# 1-Schematic_business_card_v1.net
KiCad netlist of a schematic drawn in EasyEDA
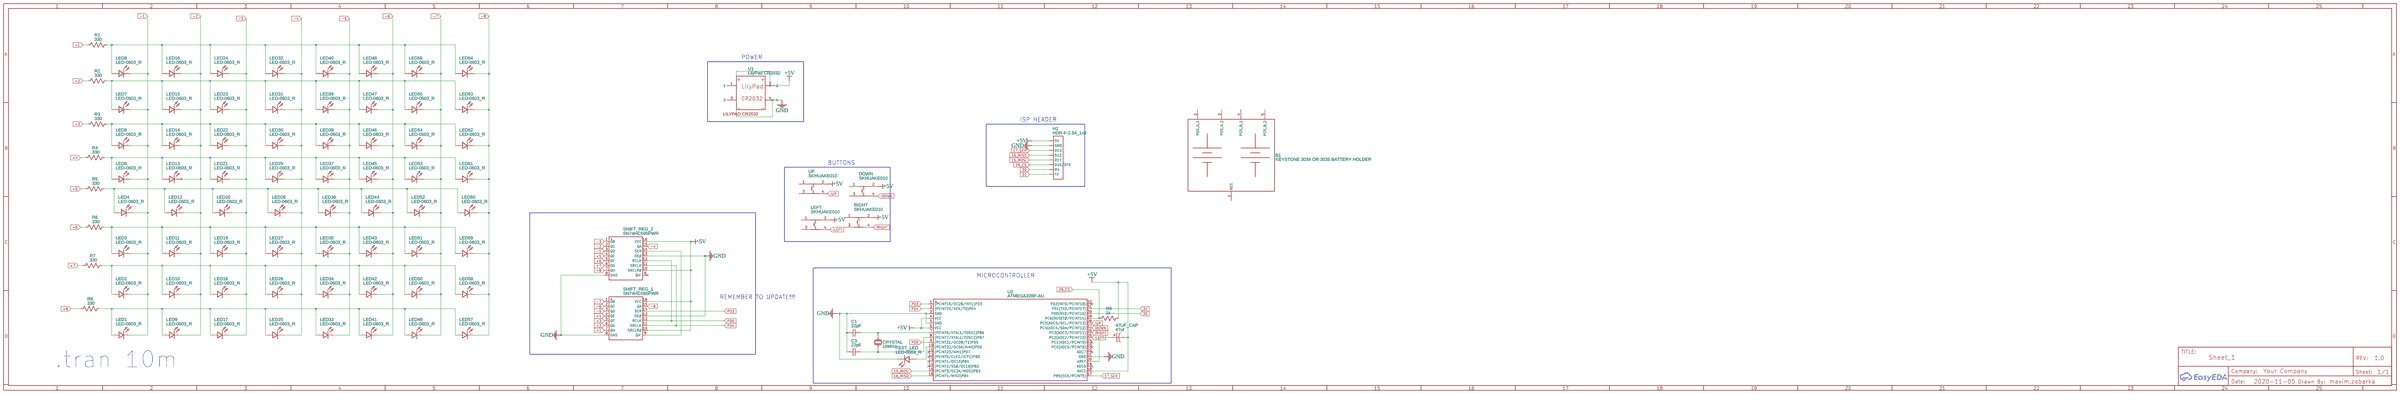
[diagram p0: schematic sheet]

(export (version "E")
  (design (tool "Eeschema 10.0.6"))
  (components
    (comp (ref "47UF_CAP") (value "47uf") (libsource (lib "") (part "C_Tan_SMD_A_US")))
    (comp (ref "B1")
      (value "KEYSTONE 3034 OR 3035 BATTERY HOLDER")
      (libsource (lib "") (part "KEYSTONE 3034 OR 3035 BATTERY HOLDER"))
    )
    (comp (ref "C1")
      (value "22pF")
      (fields
        (field (name "BOM_Manufacturer Part") "CC1206JKNPOCBN220")
        (field (name "BOM_Supplier Part") "C107174")
      )
      (libsource (lib "") (part "CC1206JKNPOCBN220"))
    )
    (comp (ref "C3")
      (value "22pF")
      (fields
        (field (name "BOM_Manufacturer Part") "CC1206JKNPOCBN220")
        (field (name "BOM_Supplier Part") "C107174")
      )
      (libsource (lib "") (part "CC1206JKNPOCBN220"))
    )
    (comp (ref "CRYSTAL")
      (value "16MHz")
      (fields
        (field (name "BOM_Manufacturer Part") "C16000J119")
        (field (name "BOM_Supplier Part") "C259047")
      )
      (libsource (lib "") (part "C16000J119"))
    )
    (comp (ref "DOWN")
      (value "SKHUAKE010")
      (fields (field (name "BOM_Supplier Part") "C262397"))
      (libsource (lib "") (part "SKHUAKE010"))
    )
    (comp (ref "H2")
      (value "HDR-F-2.54_1x8")
      (fields (field (name "BOM_Supplier Part") "C225505"))
      (libsource (lib "") (part "HDR-F-2.54_1x8"))
    )
    (comp (ref "LED1")
      (value "LED-0603_R")
      (fields
        (field (name "BOM_Manufacturer Part") "19-217/R6C-AL1M2VY/3T")
        (field (name "BOM_Supplier Part") "C72044")
      )
      (libsource (lib "") (part "LED-0603_R"))
    )
    (comp (ref "LED2")
      (value "LED-0603_R")
      (fields
        (field (name "BOM_Manufacturer Part") "19-217/R6C-AL1M2VY/3T")
        (field (name "BOM_Supplier Part") "C72044")
      )
      (libsource (lib "") (part "LED-0603_R"))
    )
    (comp (ref "LED3")
      (value "LED-0603_R")
      (fields
        (field (name "BOM_Manufacturer Part") "19-217/R6C-AL1M2VY/3T")
        (field (name "BOM_Supplier Part") "C72044")
      )
      (libsource (lib "") (part "LED-0603_R"))
    )
    (comp (ref "LED4")
      (value "LED-0603_R")
      (fields
        (field (name "BOM_Manufacturer Part") "19-217/R6C-AL1M2VY/3T")
        (field (name "BOM_Supplier Part") "C72044")
      )
      (libsource (lib "") (part "LED-0603_R"))
    )
    (comp (ref "LED5")
      (value "LED-0603_R")
      (fields
        (field (name "BOM_Manufacturer Part") "19-217/R6C-AL1M2VY/3T")
        (field (name "BOM_Supplier Part") "C72044")
      )
      (libsource (lib "") (part "LED-0603_R"))
    )
    (comp (ref "LED6")
      (value "LED-0603_R")
      (fields
        (field (name "BOM_Manufacturer Part") "19-217/R6C-AL1M2VY/3T")
        (field (name "BOM_Supplier Part") "C72044")
      )
      (libsource (lib "") (part "LED-0603_R"))
    )
    (comp (ref "LED7")
      (value "LED-0603_R")
      (fields
        (field (name "BOM_Manufacturer Part") "19-217/R6C-AL1M2VY/3T")
        (field (name "BOM_Supplier Part") "C72044")
      )
      (libsource (lib "") (part "LED-0603_R"))
    )
    (comp (ref "LED8")
      (value "LED-0603_R")
      (fields
        (field (name "BOM_Manufacturer Part") "19-217/R6C-AL1M2VY/3T")
        (field (name "BOM_Supplier Part") "C72044")
      )
      (libsource (lib "") (part "LED-0603_R"))
    )
    (comp (ref "LED9")
      (value "LED-0603_R")
      (fields
        (field (name "BOM_Manufacturer Part") "19-217/R6C-AL1M2VY/3T")
        (field (name "BOM_Supplier Part") "C72044")
      )
      (libsource (lib "") (part "LED-0603_R"))
    )
    (comp (ref "LED10")
      (value "LED-0603_R")
      (fields
        (field (name "BOM_Manufacturer Part") "19-217/R6C-AL1M2VY/3T")
        (field (name "BOM_Supplier Part") "C72044")
      )
      (libsource (lib "") (part "LED-0603_R"))
    )
    (comp (ref "LED11")
      (value "LED-0603_R")
      (fields
        (field (name "BOM_Manufacturer Part") "19-217/R6C-AL1M2VY/3T")
        (field (name "BOM_Supplier Part") "C72044")
      )
      (libsource (lib "") (part "LED-0603_R"))
    )
    (comp (ref "LED12")
      (value "LED-0603_R")
      (fields
        (field (name "BOM_Manufacturer Part") "19-217/R6C-AL1M2VY/3T")
        (field (name "BOM_Supplier Part") "C72044")
      )
      (libsource (lib "") (part "LED-0603_R"))
    )
    (comp (ref "LED13")
      (value "LED-0603_R")
      (fields
        (field (name "BOM_Manufacturer Part") "19-217/R6C-AL1M2VY/3T")
        (field (name "BOM_Supplier Part") "C72044")
      )
      (libsource (lib "") (part "LED-0603_R"))
    )
    (comp (ref "LED14")
      (value "LED-0603_R")
      (fields
        (field (name "BOM_Manufacturer Part") "19-217/R6C-AL1M2VY/3T")
        (field (name "BOM_Supplier Part") "C72044")
      )
      (libsource (lib "") (part "LED-0603_R"))
    )
    (comp (ref "LED15")
      (value "LED-0603_R")
      (fields
        (field (name "BOM_Manufacturer Part") "19-217/R6C-AL1M2VY/3T")
        (field (name "BOM_Supplier Part") "C72044")
      )
      (libsource (lib "") (part "LED-0603_R"))
    )
    (comp (ref "LED16")
      (value "LED-0603_R")
      (fields
        (field (name "BOM_Manufacturer Part") "19-217/R6C-AL1M2VY/3T")
        (field (name "BOM_Supplier Part") "C72044")
      )
      (libsource (lib "") (part "LED-0603_R"))
    )
    (comp (ref "LED17")
      (value "LED-0603_R")
      (fields
        (field (name "BOM_Manufacturer Part") "19-217/R6C-AL1M2VY/3T")
        (field (name "BOM_Supplier Part") "C72044")
      )
      (libsource (lib "") (part "LED-0603_R"))
    )
    (comp (ref "LED18")
      (value "LED-0603_R")
      (fields
        (field (name "BOM_Manufacturer Part") "19-217/R6C-AL1M2VY/3T")
        (field (name "BOM_Supplier Part") "C72044")
      )
      (libsource (lib "") (part "LED-0603_R"))
    )
    (comp (ref "LED19")
      (value "LED-0603_R")
      (fields
        (field (name "BOM_Manufacturer Part") "19-217/R6C-AL1M2VY/3T")
        (field (name "BOM_Supplier Part") "C72044")
      )
      (libsource (lib "") (part "LED-0603_R"))
    )
    (comp (ref "LED20")
      (value "LED-0603_R")
      (fields
        (field (name "BOM_Manufacturer Part") "19-217/R6C-AL1M2VY/3T")
        (field (name "BOM_Supplier Part") "C72044")
      )
      (libsource (lib "") (part "LED-0603_R"))
    )
    (comp (ref "LED21")
      (value "LED-0603_R")
      (fields
        (field (name "BOM_Manufacturer Part") "19-217/R6C-AL1M2VY/3T")
        (field (name "BOM_Supplier Part") "C72044")
      )
      (libsource (lib "") (part "LED-0603_R"))
    )
    (comp (ref "LED22")
      (value "LED-0603_R")
      (fields
        (field (name "BOM_Manufacturer Part") "19-217/R6C-AL1M2VY/3T")
        (field (name "BOM_Supplier Part") "C72044")
      )
      (libsource (lib "") (part "LED-0603_R"))
    )
    (comp (ref "LED23")
      (value "LED-0603_R")
      (fields
        (field (name "BOM_Manufacturer Part") "19-217/R6C-AL1M2VY/3T")
        (field (name "BOM_Supplier Part") "C72044")
      )
      (libsource (lib "") (part "LED-0603_R"))
    )
    (comp (ref "LED24")
      (value "LED-0603_R")
      (fields
        (field (name "BOM_Manufacturer Part") "19-217/R6C-AL1M2VY/3T")
        (field (name "BOM_Supplier Part") "C72044")
      )
      (libsource (lib "") (part "LED-0603_R"))
    )
    (comp (ref "LED25")
      (value "LED-0603_R")
      (fields
        (field (name "BOM_Manufacturer Part") "19-217/R6C-AL1M2VY/3T")
        (field (name "BOM_Supplier Part") "C72044")
      )
      (libsource (lib "") (part "LED-0603_R"))
    )
    (comp (ref "LED26")
      (value "LED-0603_R")
      (fields
        (field (name "BOM_Manufacturer Part") "19-217/R6C-AL1M2VY/3T")
        (field (name "BOM_Supplier Part") "C72044")
      )
      (libsource (lib "") (part "LED-0603_R"))
    )
    (comp (ref "LED27")
      (value "LED-0603_R")
      (fields
        (field (name "BOM_Manufacturer Part") "19-217/R6C-AL1M2VY/3T")
        (field (name "BOM_Supplier Part") "C72044")
      )
      (libsource (lib "") (part "LED-0603_R"))
    )
    (comp (ref "LED28")
      (value "LED-0603_R")
      (fields
        (field (name "BOM_Manufacturer Part") "19-217/R6C-AL1M2VY/3T")
        (field (name "BOM_Supplier Part") "C72044")
      )
      (libsource (lib "") (part "LED-0603_R"))
    )
    (comp (ref "LED29")
      (value "LED-0603_R")
      (fields
        (field (name "BOM_Manufacturer Part") "19-217/R6C-AL1M2VY/3T")
        (field (name "BOM_Supplier Part") "C72044")
      )
      (libsource (lib "") (part "LED-0603_R"))
    )
    (comp (ref "LED30")
      (value "LED-0603_R")
      (fields
        (field (name "BOM_Manufacturer Part") "19-217/R6C-AL1M2VY/3T")
        (field (name "BOM_Supplier Part") "C72044")
      )
      (libsource (lib "") (part "LED-0603_R"))
    )
    (comp (ref "LED31")
      (value "LED-0603_R")
      (fields
        (field (name "BOM_Manufacturer Part") "19-217/R6C-AL1M2VY/3T")
        (field (name "BOM_Supplier Part") "C72044")
      )
      (libsource (lib "") (part "LED-0603_R"))
    )
    (comp (ref "LED32")
      (value "LED-0603_R")
      (fields
        (field (name "BOM_Manufacturer Part") "19-217/R6C-AL1M2VY/3T")
        (field (name "BOM_Supplier Part") "C72044")
      )
      (libsource (lib "") (part "LED-0603_R"))
    )
    (comp (ref "LED33")
      (value "LED-0603_R")
      (fields
        (field (name "BOM_Manufacturer Part") "19-217/R6C-AL1M2VY/3T")
        (field (name "BOM_Supplier Part") "C72044")
      )
      (libsource (lib "") (part "LED-0603_R"))
    )
    (comp (ref "LED34")
      (value "LED-0603_R")
      (fields
        (field (name "BOM_Manufacturer Part") "19-217/R6C-AL1M2VY/3T")
        (field (name "BOM_Supplier Part") "C72044")
      )
      (libsource (lib "") (part "LED-0603_R"))
    )
    (comp (ref "LED35")
      (value "LED-0603_R")
      (fields
        (field (name "BOM_Manufacturer Part") "19-217/R6C-AL1M2VY/3T")
        (field (name "BOM_Supplier Part") "C72044")
      )
      (libsource (lib "") (part "LED-0603_R"))
    )
    (comp (ref "LED36")
      (value "LED-0603_R")
      (fields
        (field (name "BOM_Manufacturer Part") "19-217/R6C-AL1M2VY/3T")
        (field (name "BOM_Supplier Part") "C72044")
      )
      (libsource (lib "") (part "LED-0603_R"))
    )
    (comp (ref "LED37")
      (value "LED-0603_R")
      (fields
        (field (name "BOM_Manufacturer Part") "19-217/R6C-AL1M2VY/3T")
        (field (name "BOM_Supplier Part") "C72044")
      )
      (libsource (lib "") (part "LED-0603_R"))
    )
    (comp (ref "LED38")
      (value "LED-0603_R")
      (fields
        (field (name "BOM_Manufacturer Part") "19-217/R6C-AL1M2VY/3T")
        (field (name "BOM_Supplier Part") "C72044")
      )
      (libsource (lib "") (part "LED-0603_R"))
    )
    (comp (ref "LED39")
      (value "LED-0603_R")
      (fields
        (field (name "BOM_Manufacturer Part") "19-217/R6C-AL1M2VY/3T")
        (field (name "BOM_Supplier Part") "C72044")
      )
      (libsource (lib "") (part "LED-0603_R"))
    )
    (comp (ref "LED40")
      (value "LED-0603_R")
      (fields
        (field (name "BOM_Manufacturer Part") "19-217/R6C-AL1M2VY/3T")
        (field (name "BOM_Supplier Part") "C72044")
      )
      (libsource (lib "") (part "LED-0603_R"))
    )
    (comp (ref "LED41")
      (value "LED-0603_R")
      (fields
        (field (name "BOM_Manufacturer Part") "19-217/R6C-AL1M2VY/3T")
        (field (name "BOM_Supplier Part") "C72044")
      )
      (libsource (lib "") (part "LED-0603_R"))
    )
    (comp (ref "LED42")
      (value "LED-0603_R")
      (fields
        (field (name "BOM_Manufacturer Part") "19-217/R6C-AL1M2VY/3T")
        (field (name "BOM_Supplier Part") "C72044")
      )
      (libsource (lib "") (part "LED-0603_R"))
    )
    (comp (ref "LED43")
      (value "LED-0603_R")
      (fields
        (field (name "BOM_Manufacturer Part") "19-217/R6C-AL1M2VY/3T")
        (field (name "BOM_Supplier Part") "C72044")
      )
      (libsource (lib "") (part "LED-0603_R"))
    )
    (comp (ref "LED44")
      (value "LED-0603_R")
      (fields
        (field (name "BOM_Manufacturer Part") "19-217/R6C-AL1M2VY/3T")
        (field (name "BOM_Supplier Part") "C72044")
      )
      (libsource (lib "") (part "LED-0603_R"))
    )
    (comp (ref "LED45")
      (value "LED-0603_R")
      (fields
        (field (name "BOM_Manufacturer Part") "19-217/R6C-AL1M2VY/3T")
        (field (name "BOM_Supplier Part") "C72044")
      )
      (libsource (lib "") (part "LED-0603_R"))
    )
    (comp (ref "LED46")
      (value "LED-0603_R")
      (fields
        (field (name "BOM_Manufacturer Part") "19-217/R6C-AL1M2VY/3T")
        (field (name "BOM_Supplier Part") "C72044")
      )
      (libsource (lib "") (part "LED-0603_R"))
    )
    (comp (ref "LED47")
      (value "LED-0603_R")
      (fields
        (field (name "BOM_Manufacturer Part") "19-217/R6C-AL1M2VY/3T")
        (field (name "BOM_Supplier Part") "C72044")
      )
      (libsource (lib "") (part "LED-0603_R"))
    )
    (comp (ref "LED48")
      (value "LED-0603_R")
      (fields
        (field (name "BOM_Manufacturer Part") "19-217/R6C-AL1M2VY/3T")
        (field (name "BOM_Supplier Part") "C72044")
      )
      (libsource (lib "") (part "LED-0603_R"))
    )
    (comp (ref "LED49")
      (value "LED-0603_R")
      (fields
        (field (name "BOM_Manufacturer Part") "19-217/R6C-AL1M2VY/3T")
        (field (name "BOM_Supplier Part") "C72044")
      )
      (libsource (lib "") (part "LED-0603_R"))
    )
    (comp (ref "LED50")
      (value "LED-0603_R")
      (fields
        (field (name "BOM_Manufacturer Part") "19-217/R6C-AL1M2VY/3T")
        (field (name "BOM_Supplier Part") "C72044")
      )
      (libsource (lib "") (part "LED-0603_R"))
    )
    (comp (ref "LED51")
      (value "LED-0603_R")
      (fields
        (field (name "BOM_Manufacturer Part") "19-217/R6C-AL1M2VY/3T")
        (field (name "BOM_Supplier Part") "C72044")
      )
      (libsource (lib "") (part "LED-0603_R"))
    )
    (comp (ref "LED52")
      (value "LED-0603_R")
      (fields
        (field (name "BOM_Manufacturer Part") "19-217/R6C-AL1M2VY/3T")
        (field (name "BOM_Supplier Part") "C72044")
      )
      (libsource (lib "") (part "LED-0603_R"))
    )
    (comp (ref "LED53")
      (value "LED-0603_R")
      (fields
        (field (name "BOM_Manufacturer Part") "19-217/R6C-AL1M2VY/3T")
        (field (name "BOM_Supplier Part") "C72044")
      )
      (libsource (lib "") (part "LED-0603_R"))
    )
    (comp (ref "LED54")
      (value "LED-0603_R")
      (fields
        (field (name "BOM_Manufacturer Part") "19-217/R6C-AL1M2VY/3T")
        (field (name "BOM_Supplier Part") "C72044")
      )
      (libsource (lib "") (part "LED-0603_R"))
    )
    (comp (ref "LED55")
      (value "LED-0603_R")
      (fields
        (field (name "BOM_Manufacturer Part") "19-217/R6C-AL1M2VY/3T")
        (field (name "BOM_Supplier Part") "C72044")
      )
      (libsource (lib "") (part "LED-0603_R"))
    )
    (comp (ref "LED56")
      (value "LED-0603_R")
      (fields
        (field (name "BOM_Manufacturer Part") "19-217/R6C-AL1M2VY/3T")
        (field (name "BOM_Supplier Part") "C72044")
      )
      (libsource (lib "") (part "LED-0603_R"))
    )
    (comp (ref "LED57")
      (value "LED-0603_R")
      (fields
        (field (name "BOM_Manufacturer Part") "19-217/R6C-AL1M2VY/3T")
        (field (name "BOM_Supplier Part") "C72044")
      )
      (libsource (lib "") (part "LED-0603_R"))
    )
    (comp (ref "LED58")
      (value "LED-0603_R")
      (fields
        (field (name "BOM_Manufacturer Part") "19-217/R6C-AL1M2VY/3T")
        (field (name "BOM_Supplier Part") "C72044")
      )
      (libsource (lib "") (part "LED-0603_R"))
    )
    (comp (ref "LED59")
      (value "LED-0603_R")
      (fields
        (field (name "BOM_Manufacturer Part") "19-217/R6C-AL1M2VY/3T")
        (field (name "BOM_Supplier Part") "C72044")
      )
      (libsource (lib "") (part "LED-0603_R"))
    )
    (comp (ref "LED60")
      (value "LED-0603_R")
      (fields
        (field (name "BOM_Manufacturer Part") "19-217/R6C-AL1M2VY/3T")
        (field (name "BOM_Supplier Part") "C72044")
      )
      (libsource (lib "") (part "LED-0603_R"))
    )
    (comp (ref "LED61")
      (value "LED-0603_R")
      (fields
        (field (name "BOM_Manufacturer Part") "19-217/R6C-AL1M2VY/3T")
        (field (name "BOM_Supplier Part") "C72044")
      )
      (libsource (lib "") (part "LED-0603_R"))
    )
    (comp (ref "LED62")
      (value "LED-0603_R")
      (fields
        (field (name "BOM_Manufacturer Part") "19-217/R6C-AL1M2VY/3T")
        (field (name "BOM_Supplier Part") "C72044")
      )
      (libsource (lib "") (part "LED-0603_R"))
    )
    (comp (ref "LED63")
      (value "LED-0603_R")
      (fields
        (field (name "BOM_Manufacturer Part") "19-217/R6C-AL1M2VY/3T")
        (field (name "BOM_Supplier Part") "C72044")
      )
      (libsource (lib "") (part "LED-0603_R"))
    )
    (comp (ref "LED64")
      (value "LED-0603_R")
      (fields
        (field (name "BOM_Manufacturer Part") "19-217/R6C-AL1M2VY/3T")
        (field (name "BOM_Supplier Part") "C72044")
      )
      (libsource (lib "") (part "LED-0603_R"))
    )
    (comp (ref "LEFT")
      (value "SKHUAKE010")
      (fields (field (name "BOM_Supplier Part") "C262397"))
      (libsource (lib "") (part "SKHUAKE010_2"))
    )
    (comp (ref "R1") (value "330") (libsource (lib "") (part "R_0603_US")))
    (comp (ref "R2") (value "330") (libsource (lib "") (part "R_0603_US_1")))
    (comp (ref "R3") (value "330") (libsource (lib "") (part "R_0603_US")))
    (comp (ref "R4") (value "330") (libsource (lib "") (part "R_0603_US")))
    (comp (ref "R5") (value "330") (libsource (lib "") (part "R_0603_US")))
    (comp (ref "R6") (value "330") (libsource (lib "") (part "R_0603_US")))
    (comp (ref "R7") (value "330") (libsource (lib "") (part "R_0603_US")))
    (comp (ref "R8") (value "330") (libsource (lib "") (part "R_0603_US")))
    (comp (ref "R9") (value "1k") (libsource (lib "") (part "R_0603_US_1")))
    (comp (ref "RIGHT")
      (value "SKHUAKE010")
      (fields (field (name "BOM_Supplier Part") "C262397"))
      (libsource (lib "") (part "SKHUAKE010_3"))
    )
    (comp (ref "SHIFT_REG_1")
      (value "SN74HC595PWR")
      (fields (field (name "BOM_Supplier Part") "C273642"))
      (libsource (lib "") (part "SN74HC595PWR"))
    )
    (comp (ref "SHIFT_REG_2")
      (value "SN74HC595PWR")
      (fields (field (name "BOM_Supplier Part") "C273642"))
      (libsource (lib "") (part "SN74HC595PWR"))
    )
    (comp (ref "TEST_LED")
      (value "LED-0603_R")
      (fields
        (field (name "BOM_Manufacturer Part") "19-217/R6C-AL1M2VY/3T")
        (field (name "BOM_Supplier Part") "C72044")
      )
      (libsource (lib "") (part "LED-0603_R_1"))
    )
    (comp (ref "U1") (value "LilyPad CR2032") (libsource (lib "") (part "LilyPad CR2032")))
    (comp (ref "U2")
      (value "ATMEGA328P-AU")
      (fields (field (name "BOM_Supplier Part") "C14877"))
      (libsource (lib "") (part "ATMEGA328P-AU"))
    )
    (comp (ref "UP")
      (value "SKHUAKE010")
      (fields (field (name "BOM_Supplier Part") "C262397"))
      (libsource (lib "") (part "SKHUAKE010_1"))
    )
  )
  (nets
    (net (code "1") (name "+1") (class "Default")
      (node (ref "R1") (pin "2") (pinfunction "2_2") (pintype "unspecified"))
      (node (ref "SHIFT_REG_1") (pin "7") (pinfunction "QH_7") (pintype "unspecified"))
    )
    (net (code "2") (name "+2") (class "Default")
      (node (ref "R2") (pin "1") (pinfunction "1_1") (pintype "unspecified"))
      (node (ref "SHIFT_REG_1") (pin "6") (pinfunction "QG_6") (pintype "unspecified"))
    )
    (net (code "3") (name "+3") (class "Default")
      (node (ref "R3") (pin "2") (pinfunction "2_2") (pintype "unspecified"))
      (node (ref "SHIFT_REG_1") (pin "5") (pinfunction "QF_5") (pintype "unspecified"))
    )
    (net (code "4") (name "+4") (class "Default")
      (node (ref "R4") (pin "2") (pinfunction "2_2") (pintype "unspecified"))
      (node (ref "SHIFT_REG_1") (pin "4") (pinfunction "QE_4") (pintype "unspecified"))
    )
    (net (code "5") (name "+5") (class "Default")
      (node (ref "R5") (pin "2") (pinfunction "2_2") (pintype "unspecified"))
      (node (ref "SHIFT_REG_2") (pin "4") (pinfunction "QE_4") (pintype "unspecified"))
    )
    (net (code "6") (name "+5V") (class "Default")
      (node (ref "47UF_CAP") (pin "2") (pinfunction "2_2") (pintype "unspecified"))
      (node (ref "DOWN") (pin "2") (pinfunction "2_2") (pintype "unspecified"))
      (node (ref "H2") (pin "1") (pinfunction "5V_1") (pintype "unspecified"))
      (node (ref "LEFT") (pin "2") (pinfunction "2_2") (pintype "unspecified"))
      (node (ref "R9") (pin "2") (pinfunction "2_2") (pintype "unspecified"))
      (node (ref "RIGHT") (pin "2") (pinfunction "2_2") (pintype "unspecified"))
      (node (ref "SHIFT_REG_1") (pin "10") (pinfunction "SRCLR#_10") (pintype "unspecified"))
      (node (ref "SHIFT_REG_1") (pin "16") (pinfunction "VCC_16") (pintype "unspecified"))
      (node (ref "SHIFT_REG_2") (pin "10") (pinfunction "SRCLR#_10") (pintype "unspecified"))
      (node (ref "SHIFT_REG_2") (pin "16") (pinfunction "VCC_16") (pintype "unspecified"))
      (node (ref "U1") (pin "1") (pinfunction "1_1") (pintype "unspecified"))
      (node (ref "U1") (pin "2") (pinfunction "2_2") (pintype "unspecified"))
      (node (ref "U2") (pin "18") (pinfunction "AVCC_18") (pintype "unspecified"))
      (node (ref "U2") (pin "4") (pinfunction "VCC_4") (pintype "unspecified"))
      (node (ref "U2") (pin "6") (pinfunction "VCC_6") (pintype "unspecified"))
      (node (ref "UP") (pin "2") (pinfunction "2_2") (pintype "unspecified"))
    )
    (net (code "7") (name "+6") (class "Default")
      (node (ref "R6") (pin "2") (pinfunction "2_2") (pintype "unspecified"))
      (node (ref "SHIFT_REG_2") (pin "5") (pinfunction "QF_5") (pintype "unspecified"))
    )
    (net (code "8") (name "+7") (class "Default")
      (node (ref "R7") (pin "2") (pinfunction "2_2") (pintype "unspecified"))
      (node (ref "SHIFT_REG_2") (pin "6") (pinfunction "QG_6") (pintype "unspecified"))
    )
    (net (code "9") (name "+8") (class "Default")
      (node (ref "R8") (pin "2") (pinfunction "2_2") (pintype "unspecified"))
      (node (ref "SHIFT_REG_2") (pin "7") (pinfunction "QH_7") (pintype "unspecified"))
    )
    (net (code "10") (name "-1") (class "Default")
      (node (ref "LED1") (pin "2") (pinfunction "2_2") (pintype "unspecified"))
      (node (ref "LED2") (pin "2") (pinfunction "2_2") (pintype "unspecified"))
      (node (ref "LED3") (pin "2") (pinfunction "2_2") (pintype "unspecified"))
      (node (ref "LED4") (pin "2") (pinfunction "2_2") (pintype "unspecified"))
      (node (ref "LED5") (pin "2") (pinfunction "2_2") (pintype "unspecified"))
      (node (ref "LED6") (pin "2") (pinfunction "2_2") (pintype "unspecified"))
      (node (ref "LED7") (pin "2") (pinfunction "2_2") (pintype "unspecified"))
      (node (ref "LED8") (pin "2") (pinfunction "2_2") (pintype "unspecified"))
      (node (ref "SHIFT_REG_2") (pin "3") (pinfunction "QD_3") (pintype "unspecified"))
    )
    (net (code "11") (name "-2") (class "Default")
      (node (ref "LED10") (pin "2") (pinfunction "2_2") (pintype "unspecified"))
      (node (ref "LED11") (pin "2") (pinfunction "2_2") (pintype "unspecified"))
      (node (ref "LED12") (pin "2") (pinfunction "2_2") (pintype "unspecified"))
      (node (ref "LED13") (pin "2") (pinfunction "2_2") (pintype "unspecified"))
      (node (ref "LED14") (pin "2") (pinfunction "2_2") (pintype "unspecified"))
      (node (ref "LED15") (pin "2") (pinfunction "2_2") (pintype "unspecified"))
      (node (ref "LED16") (pin "2") (pinfunction "2_2") (pintype "unspecified"))
      (node (ref "LED9") (pin "2") (pinfunction "2_2") (pintype "unspecified"))
      (node (ref "SHIFT_REG_2") (pin "2") (pinfunction "QC_2") (pintype "unspecified"))
    )
    (net (code "12") (name "-3") (class "Default")
      (node (ref "LED17") (pin "2") (pinfunction "2_2") (pintype "unspecified"))
      (node (ref "LED18") (pin "2") (pinfunction "2_2") (pintype "unspecified"))
      (node (ref "LED19") (pin "2") (pinfunction "2_2") (pintype "unspecified"))
      (node (ref "LED20") (pin "2") (pinfunction "2_2") (pintype "unspecified"))
      (node (ref "LED21") (pin "2") (pinfunction "2_2") (pintype "unspecified"))
      (node (ref "LED22") (pin "2") (pinfunction "2_2") (pintype "unspecified"))
      (node (ref "LED23") (pin "2") (pinfunction "2_2") (pintype "unspecified"))
      (node (ref "LED24") (pin "2") (pinfunction "2_2") (pintype "unspecified"))
      (node (ref "SHIFT_REG_2") (pin "1") (pinfunction "QB_1") (pintype "unspecified"))
    )
    (net (code "13") (name "-4") (class "Default")
      (node (ref "LED25") (pin "2") (pinfunction "2_2") (pintype "unspecified"))
      (node (ref "LED26") (pin "2") (pinfunction "2_2") (pintype "unspecified"))
      (node (ref "LED27") (pin "2") (pinfunction "2_2") (pintype "unspecified"))
      (node (ref "LED28") (pin "2") (pinfunction "2_2") (pintype "unspecified"))
      (node (ref "LED29") (pin "2") (pinfunction "2_2") (pintype "unspecified"))
      (node (ref "LED30") (pin "2") (pinfunction "2_2") (pintype "unspecified"))
      (node (ref "LED31") (pin "2") (pinfunction "2_2") (pintype "unspecified"))
      (node (ref "LED32") (pin "2") (pinfunction "2_2") (pintype "unspecified"))
      (node (ref "SHIFT_REG_2") (pin "15") (pinfunction "QA_15") (pintype "unspecified"))
    )
    (net (code "14") (name "-5") (class "Default")
      (node (ref "LED33") (pin "2") (pinfunction "2_2") (pintype "unspecified"))
      (node (ref "LED34") (pin "2") (pinfunction "2_2") (pintype "unspecified"))
      (node (ref "LED35") (pin "2") (pinfunction "2_2") (pintype "unspecified"))
      (node (ref "LED36") (pin "2") (pinfunction "2_2") (pintype "unspecified"))
      (node (ref "LED37") (pin "2") (pinfunction "2_2") (pintype "unspecified"))
      (node (ref "LED38") (pin "2") (pinfunction "2_2") (pintype "unspecified"))
      (node (ref "LED39") (pin "2") (pinfunction "2_2") (pintype "unspecified"))
      (node (ref "LED40") (pin "2") (pinfunction "2_2") (pintype "unspecified"))
      (node (ref "SHIFT_REG_1") (pin "3") (pinfunction "QD_3") (pintype "unspecified"))
    )
    (net (code "15") (name "-6") (class "Default")
      (node (ref "LED41") (pin "2") (pinfunction "2_2") (pintype "unspecified"))
      (node (ref "LED42") (pin "2") (pinfunction "2_2") (pintype "unspecified"))
      (node (ref "LED43") (pin "2") (pinfunction "2_2") (pintype "unspecified"))
      (node (ref "LED44") (pin "2") (pinfunction "2_2") (pintype "unspecified"))
      (node (ref "LED45") (pin "2") (pinfunction "2_2") (pintype "unspecified"))
      (node (ref "LED46") (pin "2") (pinfunction "2_2") (pintype "unspecified"))
      (node (ref "LED47") (pin "2") (pinfunction "2_2") (pintype "unspecified"))
      (node (ref "LED48") (pin "2") (pinfunction "2_2") (pintype "unspecified"))
      (node (ref "SHIFT_REG_1") (pin "2") (pinfunction "QC_2") (pintype "unspecified"))
    )
    (net (code "16") (name "-7") (class "Default")
      (node (ref "LED49") (pin "2") (pinfunction "2_2") (pintype "unspecified"))
      (node (ref "LED50") (pin "2") (pinfunction "2_2") (pintype "unspecified"))
      (node (ref "LED51") (pin "2") (pinfunction "2_2") (pintype "unspecified"))
      (node (ref "LED52") (pin "2") (pinfunction "2_2") (pintype "unspecified"))
      (node (ref "LED53") (pin "2") (pinfunction "2_2") (pintype "unspecified"))
      (node (ref "LED54") (pin "2") (pinfunction "2_2") (pintype "unspecified"))
      (node (ref "LED55") (pin "2") (pinfunction "2_2") (pintype "unspecified"))
      (node (ref "LED56") (pin "2") (pinfunction "2_2") (pintype "unspecified"))
      (node (ref "SHIFT_REG_1") (pin "1") (pinfunction "QB_1") (pintype "unspecified"))
    )
    (net (code "17") (name "-8") (class "Default")
      (node (ref "LED57") (pin "2") (pinfunction "2_2") (pintype "unspecified"))
      (node (ref "LED58") (pin "2") (pinfunction "2_2") (pintype "unspecified"))
      (node (ref "LED59") (pin "2") (pinfunction "2_2") (pintype "unspecified"))
      (node (ref "LED60") (pin "2") (pinfunction "2_2") (pintype "unspecified"))
      (node (ref "LED61") (pin "2") (pinfunction "2_2") (pintype "unspecified"))
      (node (ref "LED62") (pin "2") (pinfunction "2_2") (pintype "unspecified"))
      (node (ref "LED63") (pin "2") (pinfunction "2_2") (pintype "unspecified"))
      (node (ref "LED64") (pin "2") (pinfunction "2_2") (pintype "unspecified"))
      (node (ref "SHIFT_REG_1") (pin "15") (pinfunction "QA_15") (pintype "unspecified"))
    )
    (net (code "18") (name "15_MOSI") (class "Default")
      (node (ref "H2") (pin "5") (pinfunction "D11_5") (pintype "unspecified"))
      (node (ref "U2") (pin "15") (pinfunction "(PCINT3/OC2A/MOSI)PB3_15") (pintype "unspecified"))
    )
    (net (code "19") (name "16_MISO") (class "Default")
      (node (ref "H2") (pin "4") (pinfunction "D12_4") (pintype "unspecified"))
      (node (ref "U2") (pin "16") (pinfunction "(PCINT4/MISO)PB4_16") (pintype "unspecified"))
    )
    (net (code "20") (name "17_SCK") (class "Default")
      (node (ref "H2") (pin "3") (pinfunction "D13_3") (pintype "unspecified"))
      (node (ref "U2") (pin "17") (pinfunction "PB5(SCK/PCINT5)_17") (pintype "unspecified"))
    )
    (net (code "21") (name "29_CS") (class "Default")
      (node (ref "H2") (pin "6") (pinfunction "D10/DTR_6") (pintype "unspecified"))
      (node (ref "R9") (pin "1") (pinfunction "1_1") (pintype "unspecified"))
      (node (ref "U2") (pin "29") (pinfunction "PC6(RESET#/PCINT14)_29") (pintype "unspecified"))
    )
    (net (code "22") (name "30") (class "Default")
      (node (ref "H2") (pin "7") (pinfunction "RX_7") (pintype "unspecified"))
      (node (ref "U2") (pin "30") (pinfunction "PD0(RXD/PCINT16)_30") (pintype "unspecified"))
    )
    (net (code "23") (name "31") (class "Default")
      (node (ref "H2") (pin "8") (pinfunction "TX_8") (pintype "unspecified"))
      (node (ref "U2") (pin "31") (pinfunction "PD1(TXD/PCINT17)_31") (pintype "unspecified"))
    )
    (net (code "24") (name "GND") (class "Default")
      (node (ref "C1") (pin "1") (pinfunction "1_1") (pintype "input"))
      (node (ref "C3") (pin "1") (pinfunction "1_1") (pintype "input"))
      (node (ref "H2") (pin "2") (pinfunction "GND_2") (pintype "unspecified"))
      (node (ref "SHIFT_REG_1") (pin "13") (pinfunction "OE#_13") (pintype "unspecified"))
      (node (ref "SHIFT_REG_1") (pin "8") (pinfunction "GND_8") (pintype "unspecified"))
      (node (ref "SHIFT_REG_2") (pin "13") (pinfunction "OE#_13") (pintype "unspecified"))
      (node (ref "SHIFT_REG_2") (pin "8") (pinfunction "GND_8") (pintype "unspecified"))
      (node (ref "TEST_LED") (pin "2") (pinfunction "2_2") (pintype "unspecified"))
      (node (ref "U1") (pin "3") (pinfunction "3_3") (pintype "unspecified"))
      (node (ref "U1") (pin "4") (pinfunction "4_4") (pintype "unspecified"))
      (node (ref "U2") (pin "21") (pinfunction "GND_21") (pintype "unspecified"))
      (node (ref "U2") (pin "3") (pinfunction "GND_3") (pintype "unspecified"))
      (node (ref "U2") (pin "5") (pinfunction "GND_5") (pintype "unspecified"))
    )
    (net (code "25") (name "IDOWN") (class "Default")
      (node (ref "DOWN") (pin "4") (pinfunction "4_4") (pintype "unspecified"))
      (node (ref "U2") (pin "27") (pinfunction "PC4(ADC4/SDA/PCINT12)_27") (pintype "unspecified"))
    )
    (net (code "26") (name "ILEFT") (class "Default")
      (node (ref "LEFT") (pin "4") (pinfunction "4_4") (pintype "unspecified"))
      (node (ref "U2") (pin "25") (pinfunction "PC2(ADC2/PCINT10)_25") (pintype "unspecified"))
    )
    (net (code "27") (name "IRIGHT") (class "Default")
      (node (ref "RIGHT") (pin "4") (pinfunction "4_4") (pintype "unspecified"))
      (node (ref "U2") (pin "26") (pinfunction "PC3(ADC3/PCINT11)_26") (pintype "unspecified"))
    )
    (net (code "28") (name "IUP") (class "Default")
      (node (ref "U2") (pin "28") (pinfunction "PC5(ADC5/SCL/PCINT13)_28") (pintype "unspecified"))
      (node (ref "UP") (pin "4") (pinfunction "4_4") (pintype "unspecified"))
    )
    (net (code "29") (name "Net-(CRYSTAL-OSC1)") (class "Default")
      (node (ref "C1") (pin "2") (pinfunction "2_2") (pintype "input"))
      (node (ref "CRYSTAL") (pin "1") (pinfunction "OSC1_1") (pintype "input"))
      (node (ref "U2") (pin "7") (pinfunction "(PCINT6/XTAL1/TOSC1)PB6_7") (pintype "unspecified"))
    )
    (net (code "30") (name "Net-(CRYSTAL-OSC2)") (class "Default")
      (node (ref "C3") (pin "2") (pinfunction "2_2") (pintype "input"))
      (node (ref "CRYSTAL") (pin "2") (pinfunction "OSC2_2") (pintype "input"))
      (node (ref "U2") (pin "8") (pinfunction "(PCINT7/XTAL2/TOSC2)PB7_8") (pintype "unspecified"))
    )
    (net (code "31") (name "Net-(LED1-Pad1)") (class "Default")
      (node (ref "LED1") (pin "1") (pinfunction "1_1") (pintype "unspecified"))
      (node (ref "LED17") (pin "1") (pinfunction "1_1") (pintype "unspecified"))
      (node (ref "LED25") (pin "1") (pinfunction "1_1") (pintype "unspecified"))
      (node (ref "LED33") (pin "1") (pinfunction "1_1") (pintype "unspecified"))
      (node (ref "LED41") (pin "1") (pinfunction "1_1") (pintype "unspecified"))
      (node (ref "LED49") (pin "1") (pinfunction "1_1") (pintype "unspecified"))
      (node (ref "LED57") (pin "1") (pinfunction "1_1") (pintype "unspecified"))
      (node (ref "LED9") (pin "1") (pinfunction "1_1") (pintype "unspecified"))
      (node (ref "R8") (pin "1") (pinfunction "1_1") (pintype "unspecified"))
    )
    (net (code "32") (name "Net-(LED10-Pad1)") (class "Default")
      (node (ref "LED10") (pin "1") (pinfunction "1_1") (pintype "unspecified"))
      (node (ref "LED18") (pin "1") (pinfunction "1_1") (pintype "unspecified"))
      (node (ref "LED2") (pin "1") (pinfunction "1_1") (pintype "unspecified"))
      (node (ref "LED26") (pin "1") (pinfunction "1_1") (pintype "unspecified"))
      (node (ref "LED34") (pin "1") (pinfunction "1_1") (pintype "unspecified"))
      (node (ref "LED42") (pin "1") (pinfunction "1_1") (pintype "unspecified"))
      (node (ref "LED50") (pin "1") (pinfunction "1_1") (pintype "unspecified"))
      (node (ref "LED58") (pin "1") (pinfunction "1_1") (pintype "unspecified"))
      (node (ref "R7") (pin "1") (pinfunction "1_1") (pintype "unspecified"))
    )
    (net (code "33") (name "Net-(LED11-Pad1)") (class "Default")
      (node (ref "LED11") (pin "1") (pinfunction "1_1") (pintype "unspecified"))
      (node (ref "LED19") (pin "1") (pinfunction "1_1") (pintype "unspecified"))
      (node (ref "LED27") (pin "1") (pinfunction "1_1") (pintype "unspecified"))
      (node (ref "LED3") (pin "1") (pinfunction "1_1") (pintype "unspecified"))
      (node (ref "LED35") (pin "1") (pinfunction "1_1") (pintype "unspecified"))
      (node (ref "LED43") (pin "1") (pinfunction "1_1") (pintype "unspecified"))
      (node (ref "LED51") (pin "1") (pinfunction "1_1") (pintype "unspecified"))
      (node (ref "LED59") (pin "1") (pinfunction "1_1") (pintype "unspecified"))
      (node (ref "R6") (pin "1") (pinfunction "1_1") (pintype "unspecified"))
    )
    (net (code "34") (name "Net-(LED12-Pad1)") (class "Default")
      (node (ref "LED12") (pin "1") (pinfunction "1_1") (pintype "unspecified"))
      (node (ref "LED20") (pin "1") (pinfunction "1_1") (pintype "unspecified"))
      (node (ref "LED28") (pin "1") (pinfunction "1_1") (pintype "unspecified"))
      (node (ref "LED36") (pin "1") (pinfunction "1_1") (pintype "unspecified"))
      (node (ref "LED4") (pin "1") (pinfunction "1_1") (pintype "unspecified"))
      (node (ref "LED44") (pin "1") (pinfunction "1_1") (pintype "unspecified"))
      (node (ref "LED52") (pin "1") (pinfunction "1_1") (pintype "unspecified"))
      (node (ref "LED60") (pin "1") (pinfunction "1_1") (pintype "unspecified"))
      (node (ref "R5") (pin "1") (pinfunction "1_1") (pintype "unspecified"))
    )
    (net (code "35") (name "Net-(LED13-Pad1)") (class "Default")
      (node (ref "LED13") (pin "1") (pinfunction "1_1") (pintype "unspecified"))
      (node (ref "LED21") (pin "1") (pinfunction "1_1") (pintype "unspecified"))
      (node (ref "LED29") (pin "1") (pinfunction "1_1") (pintype "unspecified"))
      (node (ref "LED37") (pin "1") (pinfunction "1_1") (pintype "unspecified"))
      (node (ref "LED45") (pin "1") (pinfunction "1_1") (pintype "unspecified"))
      (node (ref "LED5") (pin "1") (pinfunction "1_1") (pintype "unspecified"))
      (node (ref "LED53") (pin "1") (pinfunction "1_1") (pintype "unspecified"))
      (node (ref "LED61") (pin "1") (pinfunction "1_1") (pintype "unspecified"))
      (node (ref "R4") (pin "1") (pinfunction "1_1") (pintype "unspecified"))
    )
    (net (code "36") (name "Net-(LED14-Pad1)") (class "Default")
      (node (ref "LED14") (pin "1") (pinfunction "1_1") (pintype "unspecified"))
      (node (ref "LED22") (pin "1") (pinfunction "1_1") (pintype "unspecified"))
      (node (ref "LED30") (pin "1") (pinfunction "1_1") (pintype "unspecified"))
      (node (ref "LED38") (pin "1") (pinfunction "1_1") (pintype "unspecified"))
      (node (ref "LED46") (pin "1") (pinfunction "1_1") (pintype "unspecified"))
      (node (ref "LED54") (pin "1") (pinfunction "1_1") (pintype "unspecified"))
      (node (ref "LED6") (pin "1") (pinfunction "1_1") (pintype "unspecified"))
      (node (ref "LED62") (pin "1") (pinfunction "1_1") (pintype "unspecified"))
      (node (ref "R3") (pin "1") (pinfunction "1_1") (pintype "unspecified"))
    )
    (net (code "37") (name "Net-(LED15-Pad1)") (class "Default")
      (node (ref "LED15") (pin "1") (pinfunction "1_1") (pintype "unspecified"))
      (node (ref "LED23") (pin "1") (pinfunction "1_1") (pintype "unspecified"))
      (node (ref "LED31") (pin "1") (pinfunction "1_1") (pintype "unspecified"))
      (node (ref "LED39") (pin "1") (pinfunction "1_1") (pintype "unspecified"))
      (node (ref "LED47") (pin "1") (pinfunction "1_1") (pintype "unspecified"))
      (node (ref "LED55") (pin "1") (pinfunction "1_1") (pintype "unspecified"))
      (node (ref "LED63") (pin "1") (pinfunction "1_1") (pintype "unspecified"))
      (node (ref "LED7") (pin "1") (pinfunction "1_1") (pintype "unspecified"))
      (node (ref "R2") (pin "2") (pinfunction "2_2") (pintype "unspecified"))
    )
    (net (code "38") (name "Net-(LED16-Pad1)") (class "Default")
      (node (ref "LED16") (pin "1") (pinfunction "1_1") (pintype "unspecified"))
      (node (ref "LED24") (pin "1") (pinfunction "1_1") (pintype "unspecified"))
      (node (ref "LED32") (pin "1") (pinfunction "1_1") (pintype "unspecified"))
      (node (ref "LED40") (pin "1") (pinfunction "1_1") (pintype "unspecified"))
      (node (ref "LED48") (pin "1") (pinfunction "1_1") (pintype "unspecified"))
      (node (ref "LED56") (pin "1") (pinfunction "1_1") (pintype "unspecified"))
      (node (ref "LED64") (pin "1") (pinfunction "1_1") (pintype "unspecified"))
      (node (ref "LED8") (pin "1") (pinfunction "1_1") (pintype "unspecified"))
      (node (ref "R1") (pin "1") (pinfunction "1_1") (pintype "unspecified"))
    )
    (net (code "39") (name "Net-(SHIFT_REG_1-QH')") (class "Default")
      (node (ref "SHIFT_REG_1") (pin "9") (pinfunction "QH'_9") (pintype "unspecified"))
      (node (ref "SHIFT_REG_2") (pin "14") (pinfunction "SER_14") (pintype "unspecified"))
    )
    (net (code "40") (name "Net-(U2-(PCINT22{slash}OC0A{slash}AIN0)PD6)") (class "Default")
      (node (ref "TEST_LED") (pin "1") (pinfunction "1_1") (pintype "unspecified"))
      (node (ref "U2") (pin "10") (pinfunction "(PCINT22/OC0A/AIN0)PD6_10") (pintype "unspecified"))
    )
    (net (code "41") (name "Net-(U2-AREF)") (class "Default")
      (node (ref "47UF_CAP") (pin "1") (pinfunction "1_1") (pintype "unspecified"))
      (node (ref "U2") (pin "20") (pinfunction "AREF_20") (pintype "unspecified"))
    )
    (net (code "42") (name "PD3") (class "Default")
      (node (ref "SHIFT_REG_1") (pin "14") (pinfunction "SER_14") (pintype "unspecified"))
      (node (ref "U2") (pin "1") (pinfunction "(PCINT19/OC2B/INT1)PD3_1") (pintype "unspecified"))
    )
    (net (code "43") (name "PD4") (class "Default")
      (node (ref "SHIFT_REG_1") (pin "11") (pinfunction "SRCLK_11") (pintype "unspecified"))
      (node (ref "SHIFT_REG_2") (pin "11") (pinfunction "SRCLK_11") (pintype "unspecified"))
      (node (ref "U2") (pin "2") (pinfunction "(PCINT20/XCK/T0)PD4_2") (pintype "unspecified"))
    )
    (net (code "44") (name "PD5") (class "Default")
      (node (ref "SHIFT_REG_1") (pin "12") (pinfunction "RCLK_12") (pintype "unspecified"))
      (node (ref "SHIFT_REG_2") (pin "12") (pinfunction "RCLK_12") (pintype "unspecified"))
      (node (ref "U2") (pin "9") (pinfunction "(PCINT21/OC0B/T1)PD5_9") (pintype "unspecified"))
    )
    (net (code "45") (name "unconnected-(B1-NEG-Pad1)") (class "Default")
      (node (ref "B1") (pin "1") (pinfunction "NEG_1") (pintype "unspecified"))
    )
    (net (code "46") (name "unconnected-(B1-POS_A_1-Pad2)") (class "Default")
      (node (ref "B1") (pin "2") (pinfunction "POS_A_1_2") (pintype "unspecified"))
    )
    (net (code "47") (name "unconnected-(B1-POS_A_2-Pad3)") (class "Default")
      (node (ref "B1") (pin "3") (pinfunction "POS_A_2_3") (pintype "unspecified"))
    )
    (net (code "48") (name "unconnected-(B1-POS_B_1-Pad4)") (class "Default")
      (node (ref "B1") (pin "4") (pinfunction "POS_B_1_4") (pintype "unspecified"))
    )
    (net (code "49") (name "unconnected-(B1-POS_B_2-Pad5)") (class "Default")
      (node (ref "B1") (pin "5") (pinfunction "POS_B_2_5") (pintype "unspecified"))
    )
    (net (code "50") (name "unconnected-(DOWN-Pad1)") (class "Default")
      (node (ref "DOWN") (pin "1") (pinfunction "1_1") (pintype "unspecified"))
    )
    (net (code "51") (name "unconnected-(DOWN-Pad3)") (class "Default")
      (node (ref "DOWN") (pin "3") (pinfunction "3_3") (pintype "unspecified"))
    )
    (net (code "52") (name "unconnected-(LEFT-Pad1)") (class "Default")
      (node (ref "LEFT") (pin "1") (pinfunction "1_1") (pintype "unspecified"))
    )
    (net (code "53") (name "unconnected-(LEFT-Pad3)") (class "Default")
      (node (ref "LEFT") (pin "3") (pinfunction "3_3") (pintype "unspecified"))
    )
    (net (code "54") (name "unconnected-(RIGHT-Pad1)") (class "Default")
      (node (ref "RIGHT") (pin "1") (pinfunction "1_1") (pintype "unspecified"))
    )
    (net (code "55") (name "unconnected-(RIGHT-Pad3)") (class "Default")
      (node (ref "RIGHT") (pin "3") (pinfunction "3_3") (pintype "unspecified"))
    )
    (net (code "56") (name "unconnected-(SHIFT_REG_2-QH'-Pad9)") (class "Default")
      (node (ref "SHIFT_REG_2") (pin "9") (pinfunction "QH'_9") (pintype "unspecified+no_connect"))
    )
    (net (code "57") (name "unconnected-(U2-(PCINT0{slash}CLKO{slash}ICP1)PB0-Pad12)") (class "Default")
      (node (ref "U2") (pin "12") (pinfunction "(PCINT0/CLKO/ICP1)PB0_12") (pintype "unspecified+no_connect"))
    )
    (net (code "58") (name "unconnected-(U2-(PCINT1{slash}OC1A)PB1-Pad13)") (class "Default")
      (node (ref "U2") (pin "13") (pinfunction "(PCINT1/OC1A)PB1_13") (pintype "unspecified+no_connect"))
    )
    (net (code "59") (name "unconnected-(U2-(PCINT2{slash}SS#{slash}OC1B)PB2-Pad14)") (class "Default")
      (node (ref "U2") (pin "14") (pinfunction "(PCINT2/SS#/OC1B)PB2_14") (pintype "unspecified+no_connect"))
    )
    (net (code "60") (name "unconnected-(U2-(PCINT23{slash}AIN1)PD7-Pad11)") (class "Default")
      (node (ref "U2") (pin "11") (pinfunction "(PCINT23/AIN1)PD7_11") (pintype "unspecified+no_connect"))
    )
    (net (code "61") (name "unconnected-(U2-ADC6-Pad19)") (class "Default")
      (node (ref "U2") (pin "19") (pinfunction "ADC6_19") (pintype "unspecified+no_connect"))
    )
    (net (code "62") (name "unconnected-(U2-ADC7-Pad22)") (class "Default")
      (node (ref "U2") (pin "22") (pinfunction "ADC7_22") (pintype "unspecified+no_connect"))
    )
    (net (code "63") (name "unconnected-(U2-PC0(ADC0{slash}PCINT8)-Pad23)") (class "Default")
      (node (ref "U2") (pin "23") (pinfunction "PC0(ADC0/PCINT8)_23") (pintype "unspecified+no_connect"))
    )
    (net (code "64") (name "unconnected-(U2-PC1(ADC1{slash}PCINT9)-Pad24)") (class "Default")
      (node (ref "U2") (pin "24") (pinfunction "PC1(ADC1/PCINT9)_24") (pintype "unspecified+no_connect"))
    )
    (net (code "65") (name "unconnected-(U2-PD2(INT0{slash}PCINT18)-Pad32)") (class "Default")
      (node (ref "U2") (pin "32") (pinfunction "PD2(INT0/PCINT18)_32") (pintype "unspecified+no_connect"))
    )
    (net (code "66") (name "unconnected-(UP-Pad1)") (class "Default")
      (node (ref "UP") (pin "1") (pinfunction "1_1") (pintype "unspecified"))
    )
    (net (code "67") (name "unconnected-(UP-Pad3)") (class "Default")
      (node (ref "UP") (pin "3") (pinfunction "3_3") (pintype "unspecified"))
    )
  )
)
